# 4_phy2.net
KiCad netlist of a schematic drawn in Altium Designer
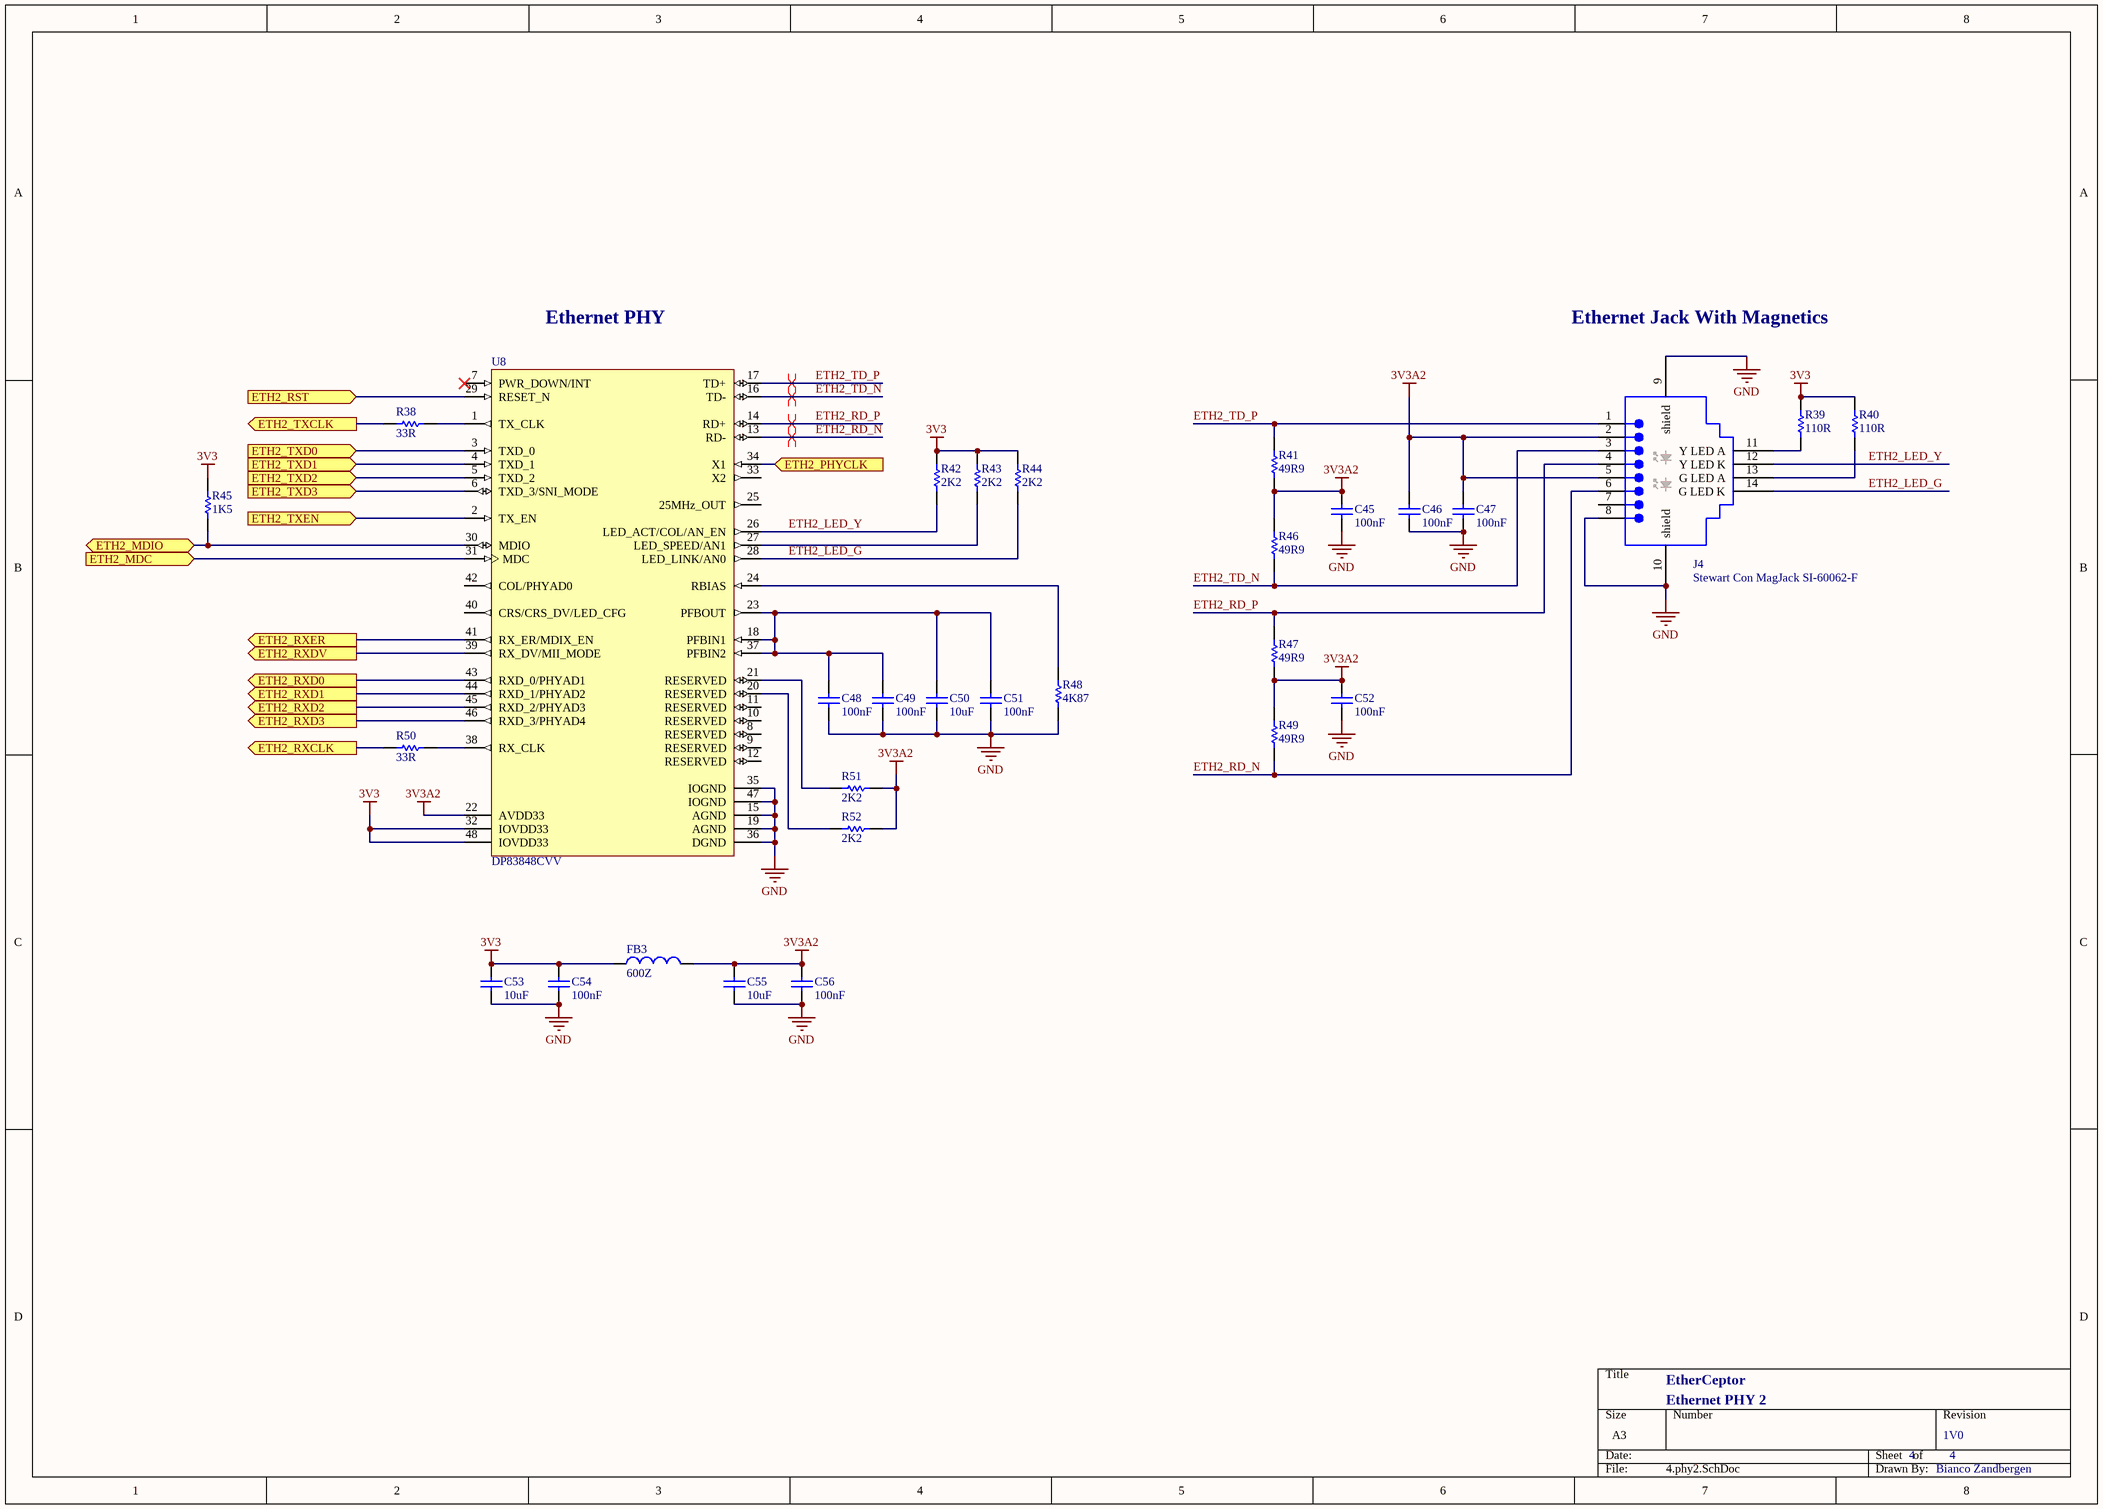
[diagram p0: 4.phy2.SchDoc]

(export (version "E")
  (design (tool "Eeschema 10.0.6"))
  (components
    (comp (ref "C45")
      (value "100nF")
      (footprint "1005[0402]_CAP2")
      (description "Capacitor")
      (fields
        (field (name "MANUFACTURER") "SAMSUNG")
        (field (name "Comment") "Cap")
        (field (name "PUBLISHER") "Altium Limited")
      )
      (libsource (lib "etherceptor") (part "Cap"))
    )
    (comp (ref "C46")
      (value "100nF")
      (footprint "1005[0402]_CAP2")
      (description "Capacitor")
      (fields
        (field (name "MANUFACTURER") "SAMSUNG")
        (field (name "Comment") "Cap")
        (field (name "PUBLISHER") "Altium Limited")
      )
      (libsource (lib "etherceptor") (part "Cap"))
    )
    (comp (ref "C47")
      (value "100nF")
      (footprint "1005[0402]_CAP2")
      (description "Capacitor")
      (fields
        (field (name "MANUFACTURER") "SAMSUNG")
        (field (name "Comment") "Cap")
        (field (name "PUBLISHER") "Altium Limited")
      )
      (libsource (lib "etherceptor") (part "Cap"))
    )
    (comp (ref "C48")
      (value "100nF")
      (footprint "1005[0402]_CAP2")
      (description "Capacitor")
      (fields
        (field (name "MANUFACTURER") "SAMSUNG")
        (field (name "Comment") "Cap")
        (field (name "PUBLISHER") "Altium Limited")
      )
      (libsource (lib "etherceptor") (part "Cap"))
    )
    (comp (ref "C49")
      (value "100nF")
      (footprint "1005[0402]_CAP2")
      (description "Capacitor")
      (fields
        (field (name "MANUFACTURER") "SAMSUNG")
        (field (name "Comment") "Cap")
        (field (name "PUBLISHER") "Altium Limited")
      )
      (libsource (lib "etherceptor") (part "Cap"))
    )
    (comp (ref "C50")
      (value "10uF")
      (footprint "1608[0603]_CAP2")
      (description "Capacitor")
      (fields
        (field (name "MANUFACTURER") "SAMSUNG")
        (field (name "Comment") "Cap")
        (field (name "PUBLISHER") "Altium Limited")
      )
      (libsource (lib "etherceptor") (part "Cap"))
    )
    (comp (ref "C51")
      (value "100nF")
      (footprint "1005[0402]_CAP2")
      (description "Capacitor")
      (fields
        (field (name "MANUFACTURER") "SAMSUNG")
        (field (name "Comment") "Cap")
        (field (name "PUBLISHER") "Altium Limited")
      )
      (libsource (lib "etherceptor") (part "Cap"))
    )
    (comp (ref "C52")
      (value "100nF")
      (footprint "1005[0402]_CAP2")
      (description "Capacitor")
      (fields
        (field (name "MANUFACTURER") "SAMSUNG")
        (field (name "Comment") "Cap")
        (field (name "PUBLISHER") "Altium Limited")
      )
      (libsource (lib "etherceptor") (part "Cap"))
    )
    (comp (ref "C53")
      (value "10uF")
      (footprint "1608[0603]_CAP2")
      (description "Capacitor")
      (fields
        (field (name "MANUFACTURER") "SAMSUNG")
        (field (name "Comment") "Cap")
        (field (name "PUBLISHER") "Altium Limited")
      )
      (libsource (lib "etherceptor") (part "Cap"))
    )
    (comp (ref "C54")
      (value "100nF")
      (footprint "1005[0402]_CAP2")
      (description "Capacitor")
      (fields
        (field (name "MANUFACTURER") "SAMSUNG")
        (field (name "Comment") "Cap")
        (field (name "PUBLISHER") "Altium Limited")
      )
      (libsource (lib "etherceptor") (part "Cap"))
    )
    (comp (ref "C55")
      (value "10uF")
      (footprint "1608[0603]_CAP2")
      (description "Capacitor")
      (fields
        (field (name "MANUFACTURER") "SAMSUNG")
        (field (name "Comment") "Cap")
        (field (name "PUBLISHER") "Altium Limited")
      )
      (libsource (lib "etherceptor") (part "Cap"))
    )
    (comp (ref "C56")
      (value "100nF")
      (footprint "1005[0402]_CAP2")
      (description "Capacitor")
      (fields
        (field (name "MANUFACTURER") "SAMSUNG")
        (field (name "Comment") "Cap")
        (field (name "PUBLISHER") "Altium Limited")
      )
      (libsource (lib "etherceptor") (part "Cap"))
    )
    (comp (ref "FB3")
      (value "600Z")
      (footprint "1005[0402]_FB2")
      (description "Ferrite Bead")
      (fields (field (name "MANUFACTURER") "MURATA") (field (name "PUBLISHER") "Altium Limited"))
      (libsource (lib "etherceptor") (part "Ferrite Bead"))
    )
    (comp (ref "J4")
      (value "Stewart Con MagJack SI-60062-F")
      (footprint "Steward Con RJ45")
      (description "Right Angle,RJ45-Keyed, Flange Mount PCB Jack")
      (fields (field (name "MANUFACTURER") "STEWART CONNECTOR") (field (name "PUBLISHER") "Altium Limited"))
      (libsource (lib "etherceptor") (part "Steward con RJ45 with magnetics"))
    )
    (comp (ref "R38")
      (value "33R")
      (footprint "1005[0402]_RES2")
      (description "Resistor")
      (fields
        (field (name "MANUFACTURER") "PANASONIC")
        (field (name "Comment") "Res")
        (field (name "PUBLISHER") "Altium Limited")
      )
      (libsource (lib "etherceptor") (part "Res"))
    )
    (comp (ref "R39")
      (value "110R")
      (footprint "1005[0402]_RES2")
      (description "Resistor")
      (fields
        (field (name "MANUFACTURER") "PANASONIC")
        (field (name "Comment") "Res")
        (field (name "PUBLISHER") "Altium Limited")
      )
      (libsource (lib "etherceptor") (part "Res"))
    )
    (comp (ref "R40")
      (value "110R")
      (footprint "1005[0402]_RES2")
      (description "Resistor")
      (fields
        (field (name "MANUFACTURER") "PANASONIC")
        (field (name "Comment") "Res")
        (field (name "PUBLISHER") "Altium Limited")
      )
      (libsource (lib "etherceptor") (part "Res"))
    )
    (comp (ref "R41")
      (value "49R9")
      (footprint "1005[0402]_RES2")
      (description "Resistor")
      (fields
        (field (name "MANUFACTURER") "PANASONIC")
        (field (name "Comment") "Res")
        (field (name "PUBLISHER") "Altium Limited")
      )
      (libsource (lib "etherceptor") (part "Res"))
    )
    (comp (ref "R42")
      (value "2K2")
      (footprint "1005[0402]_RES2")
      (description "Resistor")
      (fields
        (field (name "MANUFACTURER") "PANASONIC")
        (field (name "Comment") "Res")
        (field (name "PUBLISHER") "Altium Limited")
      )
      (libsource (lib "etherceptor") (part "Res"))
    )
    (comp (ref "R43")
      (value "2K2")
      (footprint "1005[0402]_RES2")
      (description "Resistor")
      (fields
        (field (name "MANUFACTURER") "PANASONIC")
        (field (name "Comment") "Res")
        (field (name "PUBLISHER") "Altium Limited")
      )
      (libsource (lib "etherceptor") (part "Res"))
    )
    (comp (ref "R44")
      (value "2K2")
      (footprint "1005[0402]_RES2")
      (description "Resistor")
      (fields
        (field (name "MANUFACTURER") "PANASONIC")
        (field (name "Comment") "Res")
        (field (name "PUBLISHER") "Altium Limited")
      )
      (libsource (lib "etherceptor") (part "Res"))
    )
    (comp (ref "R45")
      (value "1K5")
      (footprint "1005[0402]_RES2")
      (description "Resistor")
      (fields
        (field (name "MANUFACTURER") "PANASONIC")
        (field (name "Comment") "Res")
        (field (name "PUBLISHER") "Altium Limited")
      )
      (libsource (lib "etherceptor") (part "Res"))
    )
    (comp (ref "R46")
      (value "49R9")
      (footprint "1005[0402]_RES2")
      (description "Resistor")
      (fields
        (field (name "MANUFACTURER") "PANASONIC")
        (field (name "Comment") "Res")
        (field (name "PUBLISHER") "Altium Limited")
      )
      (libsource (lib "etherceptor") (part "Res"))
    )
    (comp (ref "R47")
      (value "49R9")
      (footprint "1005[0402]_RES2")
      (description "Resistor")
      (fields
        (field (name "MANUFACTURER") "PANASONIC")
        (field (name "Comment") "Res")
        (field (name "PUBLISHER") "Altium Limited")
      )
      (libsource (lib "etherceptor") (part "Res"))
    )
    (comp (ref "R48")
      (value "4K87")
      (footprint "1005[0402]_RES2")
      (description "Resistor")
      (fields
        (field (name "MANUFACTURER") "PANASONIC")
        (field (name "Comment") "Res")
        (field (name "PUBLISHER") "Altium Limited")
      )
      (libsource (lib "etherceptor") (part "Res"))
    )
    (comp (ref "R49")
      (value "49R9")
      (footprint "1005[0402]_RES2")
      (description "Resistor")
      (fields
        (field (name "MANUFACTURER") "PANASONIC")
        (field (name "Comment") "Res")
        (field (name "PUBLISHER") "Altium Limited")
      )
      (libsource (lib "etherceptor") (part "Res"))
    )
    (comp (ref "R50")
      (value "33R")
      (footprint "1005[0402]_RES2")
      (description "Resistor")
      (fields
        (field (name "MANUFACTURER") "PANASONIC")
        (field (name "Comment") "Res")
        (field (name "PUBLISHER") "Altium Limited")
      )
      (libsource (lib "etherceptor") (part "Res"))
    )
    (comp (ref "R51")
      (value "2K2")
      (footprint "1005[0402]_RES2")
      (description "Resistor")
      (fields
        (field (name "MANUFACTURER") "PANASONIC")
        (field (name "Comment") "Res")
        (field (name "PUBLISHER") "Altium Limited")
      )
      (libsource (lib "etherceptor") (part "Res"))
    )
    (comp (ref "R52")
      (value "2K2")
      (footprint "1005[0402]_RES2")
      (description "Resistor")
      (fields
        (field (name "MANUFACTURER") "PANASONIC")
        (field (name "Comment") "Res")
        (field (name "PUBLISHER") "Altium Limited")
      )
      (libsource (lib "etherceptor") (part "Res"))
    )
    (comp (ref "U8")
      (value "DP83848CVV")
      (footprint "TSQFP50P900X900-48M")
      (fields (field (name "MANUFACTURER") "TEXAS INSTRUMENTS") (field (name "PUBLISHER") "Altium Limited"))
      (libsource (lib "etherceptor") (part "DP83848CVV"))
    )
  )
  (nets
    (net (code "1") (name "/ETH2_LED_G") (class "Default")
      (node (ref "J4") (pin "14") (pinfunction "G_LED_K_14") (pintype "passive"))
      (node (ref "R44") (pin "1") (pinfunction "1_1") (pintype "passive"))
      (node (ref "U8") (pin "28") (pinfunction "LED_LINK/AN0_28") (pintype "output"))
    )
    (net (code "2") (name "/ETH2_LED_Y") (class "Default")
      (node (ref "J4") (pin "12") (pinfunction "Y_LED_K_12") (pintype "passive"))
      (node (ref "R42") (pin "1") (pinfunction "1_1") (pintype "passive"))
      (node (ref "U8") (pin "26") (pinfunction "LED_ACT/COL/AN_EN_26") (pintype "output"))
    )
    (net (code "3") (name "/ETH2_MDC") (class "Default")
      (node (ref "U8") (pin "31") (pinfunction "MDC_31") (pintype "input"))
    )
    (net (code "4") (name "/ETH2_MDIO") (class "Default")
      (node (ref "R45") (pin "1") (pinfunction "1_1") (pintype "passive"))
      (node (ref "U8") (pin "30") (pinfunction "MDIO_30") (pintype "bidirectional"))
    )
    (net (code "5") (name "/ETH2_PHYCLK") (class "Default")
      (node (ref "U8") (pin "34") (pinfunction "X1_34") (pintype "input"))
    )
    (net (code "6") (name "/ETH2_RD_N") (class "Default")
      (node (ref "J4") (pin "6") (pinfunction "6_6") (pintype "passive"))
      (node (ref "R49") (pin "1") (pinfunction "1_1") (pintype "passive"))
      (node (ref "U8") (pin "13") (pinfunction "RD-_13") (pintype "bidirectional"))
    )
    (net (code "7") (name "/ETH2_RD_P") (class "Default")
      (node (ref "J4") (pin "4") (pinfunction "4_4") (pintype "passive"))
      (node (ref "R47") (pin "2") (pinfunction "2_2") (pintype "passive"))
      (node (ref "U8") (pin "14") (pinfunction "RD+_14") (pintype "bidirectional"))
    )
    (net (code "8") (name "/ETH2_RST") (class "Default")
      (node (ref "U8") (pin "29") (pinfunction "RESET_N_29") (pintype "input"))
    )
    (net (code "9") (name "/ETH2_RXCLK") (class "Default")
      (node (ref "R50") (pin "1") (pinfunction "1_1") (pintype "passive"))
    )
    (net (code "10") (name "/ETH2_RXD0") (class "Default")
      (node (ref "U8") (pin "43") (pinfunction "RXD_0/PHYAD1_43") (pintype "output"))
    )
    (net (code "11") (name "/ETH2_RXD1") (class "Default")
      (node (ref "U8") (pin "44") (pinfunction "RXD_1/PHYAD2_44") (pintype "output"))
    )
    (net (code "12") (name "/ETH2_RXD2") (class "Default")
      (node (ref "U8") (pin "45") (pinfunction "RXD_2/PHYAD3_45") (pintype "output"))
    )
    (net (code "13") (name "/ETH2_RXD3") (class "Default")
      (node (ref "U8") (pin "46") (pinfunction "RXD_3/PHYAD4_46") (pintype "output"))
    )
    (net (code "14") (name "/ETH2_RXDV") (class "Default")
      (node (ref "U8") (pin "39") (pinfunction "RX_DV/MII_MODE_39") (pintype "output"))
    )
    (net (code "15") (name "/ETH2_RXER") (class "Default")
      (node (ref "U8") (pin "41") (pinfunction "RX_ER/MDIX_EN_41") (pintype "output"))
    )
    (net (code "16") (name "/ETH2_TD_N") (class "Default")
      (node (ref "J4") (pin "3") (pinfunction "3_3") (pintype "passive"))
      (node (ref "R46") (pin "1") (pinfunction "1_1") (pintype "passive"))
      (node (ref "U8") (pin "16") (pinfunction "TD-_16") (pintype "bidirectional"))
    )
    (net (code "17") (name "/ETH2_TD_P") (class "Default")
      (node (ref "J4") (pin "1") (pinfunction "1_1") (pintype "passive"))
      (node (ref "R41") (pin "2") (pinfunction "2_2") (pintype "passive"))
      (node (ref "U8") (pin "17") (pinfunction "TD+_17") (pintype "bidirectional"))
    )
    (net (code "18") (name "/ETH2_TXCLK") (class "Default")
      (node (ref "R38") (pin "1") (pinfunction "1_1") (pintype "passive"))
    )
    (net (code "19") (name "/ETH2_TXD0") (class "Default")
      (node (ref "U8") (pin "3") (pinfunction "TXD_0_3") (pintype "input"))
    )
    (net (code "20") (name "/ETH2_TXD1") (class "Default")
      (node (ref "U8") (pin "4") (pinfunction "TXD_1_4") (pintype "input"))
    )
    (net (code "21") (name "/ETH2_TXD2") (class "Default")
      (node (ref "U8") (pin "5") (pinfunction "TXD_2_5") (pintype "input"))
    )
    (net (code "22") (name "/ETH2_TXD3") (class "Default")
      (node (ref "U8") (pin "6") (pinfunction "TXD_3/SNI_MODE_6") (pintype "bidirectional"))
    )
    (net (code "23") (name "/ETH2_TXEN") (class "Default")
      (node (ref "U8") (pin "2") (pinfunction "TX_EN_2") (pintype "input"))
    )
    (net (code "24") (name "3V3") (class "Default")
      (node (ref "C53") (pin "2") (pinfunction "2_2") (pintype "passive"))
      (node (ref "C54") (pin "2") (pinfunction "2_2") (pintype "passive"))
      (node (ref "FB3") (pin "1") (pinfunction "1_1") (pintype "passive"))
      (node (ref "R39") (pin "2") (pinfunction "2_2") (pintype "passive"))
      (node (ref "R40") (pin "2") (pinfunction "2_2") (pintype "passive"))
      (node (ref "R42") (pin "2") (pinfunction "2_2") (pintype "passive"))
      (node (ref "R43") (pin "2") (pinfunction "2_2") (pintype "passive"))
      (node (ref "R44") (pin "2") (pinfunction "2_2") (pintype "passive"))
      (node (ref "R45") (pin "2") (pinfunction "2_2") (pintype "passive"))
      (node (ref "U8") (pin "32") (pinfunction "IOVDD33_32") (pintype "power_in"))
      (node (ref "U8") (pin "48") (pinfunction "IOVDD33_48") (pintype "power_in"))
    )
    (net (code "25") (name "3V3A2") (class "Default")
      (node (ref "C45") (pin "2") (pinfunction "2_2") (pintype "passive"))
      (node (ref "C46") (pin "2") (pinfunction "2_2") (pintype "passive"))
      (node (ref "C47") (pin "2") (pinfunction "2_2") (pintype "passive"))
      (node (ref "C52") (pin "2") (pinfunction "2_2") (pintype "passive"))
      (node (ref "C55") (pin "2") (pinfunction "2_2") (pintype "passive"))
      (node (ref "C56") (pin "2") (pinfunction "2_2") (pintype "passive"))
      (node (ref "FB3") (pin "2") (pinfunction "2_2") (pintype "passive"))
      (node (ref "J4") (pin "2") (pinfunction "2_2") (pintype "passive"))
      (node (ref "J4") (pin "5") (pinfunction "5_5") (pintype "passive"))
      (node (ref "R41") (pin "1") (pinfunction "1_1") (pintype "passive"))
      (node (ref "R46") (pin "2") (pinfunction "2_2") (pintype "passive"))
      (node (ref "R47") (pin "1") (pinfunction "1_1") (pintype "passive"))
      (node (ref "R49") (pin "2") (pinfunction "2_2") (pintype "passive"))
      (node (ref "R51") (pin "1") (pinfunction "1_1") (pintype "passive"))
      (node (ref "R52") (pin "1") (pinfunction "1_1") (pintype "passive"))
      (node (ref "U8") (pin "22") (pinfunction "AVDD33_22") (pintype "power_in"))
    )
    (net (code "26") (name "GND") (class "Default")
      (node (ref "C45") (pin "1") (pinfunction "1_1") (pintype "passive"))
      (node (ref "C46") (pin "1") (pinfunction "1_1") (pintype "passive"))
      (node (ref "C47") (pin "1") (pinfunction "1_1") (pintype "passive"))
      (node (ref "C48") (pin "1") (pinfunction "1_1") (pintype "passive"))
      (node (ref "C49") (pin "1") (pinfunction "1_1") (pintype "passive"))
      (node (ref "C50") (pin "1") (pinfunction "1_1") (pintype "passive"))
      (node (ref "C51") (pin "1") (pinfunction "1_1") (pintype "passive"))
      (node (ref "C52") (pin "1") (pinfunction "1_1") (pintype "passive"))
      (node (ref "C53") (pin "1") (pinfunction "1_1") (pintype "passive"))
      (node (ref "C54") (pin "1") (pinfunction "1_1") (pintype "passive"))
      (node (ref "C55") (pin "1") (pinfunction "1_1") (pintype "passive"))
      (node (ref "C56") (pin "1") (pinfunction "1_1") (pintype "passive"))
      (node (ref "J4") (pin "10") (pinfunction "shield_10") (pintype "passive"))
      (node (ref "J4") (pin "8") (pinfunction "8_8") (pintype "passive"))
      (node (ref "J4") (pin "9") (pinfunction "shield_9") (pintype "passive"))
      (node (ref "R48") (pin "1") (pinfunction "1_1") (pintype "passive"))
      (node (ref "U8") (pin "15") (pinfunction "AGND_15") (pintype "power_in"))
      (node (ref "U8") (pin "19") (pinfunction "AGND_19") (pintype "power_in"))
      (node (ref "U8") (pin "35") (pinfunction "IOGND_35") (pintype "power_in"))
      (node (ref "U8") (pin "36") (pinfunction "DGND_36") (pintype "power_in"))
      (node (ref "U8") (pin "47") (pinfunction "IOGND_47") (pintype "power_in"))
    )
    (net (code "27") (name "Net-(J4-G_LED_A)") (class "Default")
      (node (ref "J4") (pin "13") (pinfunction "G_LED_A_13") (pintype "passive"))
      (node (ref "R40") (pin "1") (pinfunction "1_1") (pintype "passive"))
    )
    (net (code "28") (name "Net-(J4-Y_LED_A)") (class "Default")
      (node (ref "J4") (pin "11") (pinfunction "Y_LED_A_11") (pintype "passive"))
      (node (ref "R39") (pin "1") (pinfunction "1_1") (pintype "passive"))
    )
    (net (code "29") (name "Net-(R51-Pad2)") (class "Default")
      (node (ref "R51") (pin "2") (pinfunction "2_2") (pintype "passive"))
      (node (ref "U8") (pin "21") (pinfunction "RESERVED_21") (pintype "bidirectional"))
    )
    (net (code "30") (name "Net-(R52-Pad2)") (class "Default")
      (node (ref "R52") (pin "2") (pinfunction "2_2") (pintype "passive"))
      (node (ref "U8") (pin "20") (pinfunction "RESERVED_20") (pintype "bidirectional"))
    )
    (net (code "31") (name "Net-(U8-LED_SPEED{slash}AN1)") (class "Default")
      (node (ref "R43") (pin "1") (pinfunction "1_1") (pintype "passive"))
      (node (ref "U8") (pin "27") (pinfunction "LED_SPEED/AN1_27") (pintype "output"))
    )
    (net (code "32") (name "Net-(U8-PFBIN1)") (class "Default")
      (node (ref "C48") (pin "2") (pinfunction "2_2") (pintype "passive"))
      (node (ref "C49") (pin "2") (pinfunction "2_2") (pintype "passive"))
      (node (ref "C50") (pin "2") (pinfunction "2_2") (pintype "passive"))
      (node (ref "C51") (pin "2") (pinfunction "2_2") (pintype "passive"))
      (node (ref "U8") (pin "18") (pinfunction "PFBIN1_18") (pintype "input"))
      (node (ref "U8") (pin "23") (pinfunction "PFBOUT_23") (pintype "output"))
      (node (ref "U8") (pin "37") (pinfunction "PFBIN2_37") (pintype "input"))
    )
    (net (code "33") (name "Net-(U8-RBIAS)") (class "Default")
      (node (ref "R48") (pin "2") (pinfunction "2_2") (pintype "passive"))
      (node (ref "U8") (pin "24") (pinfunction "RBIAS_24") (pintype "input"))
    )
    (net (code "34") (name "Net-(U8-RX_CLK)") (class "Default")
      (node (ref "R50") (pin "2") (pinfunction "2_2") (pintype "passive"))
      (node (ref "U8") (pin "38") (pinfunction "RX_CLK_38") (pintype "output"))
    )
    (net (code "35") (name "Net-(U8-TX_CLK)") (class "Default")
      (node (ref "R38") (pin "2") (pinfunction "2_2") (pintype "passive"))
      (node (ref "U8") (pin "1") (pinfunction "TX_CLK_1") (pintype "output"))
    )
    (net (code "36") (name "unconnected-(J4-Pad7)") (class "Default")
      (node (ref "J4") (pin "7") (pinfunction "7_7") (pintype "passive"))
    )
    (net (code "37") (name "unconnected-(U8-25MHz_OUT-Pad25)") (class "Default")
      (node (ref "U8") (pin "25") (pinfunction "25MHz_OUT_25") (pintype "output"))
    )
    (net (code "38") (name "unconnected-(U8-COL{slash}PHYAD0-Pad42)") (class "Default")
      (node (ref "U8") (pin "42") (pinfunction "COL/PHYAD0_42") (pintype "output"))
    )
    (net (code "39") (name "unconnected-(U8-CRS{slash}CRS_DV{slash}LED_CFG-Pad40)") (class "Default")
      (node (ref "U8") (pin "40") (pinfunction "CRS/CRS_DV/LED_CFG_40") (pintype "output"))
    )
    (net (code "40") (name "unconnected-(U8-PWR_DOWN{slash}INT-Pad7)") (class "Default")
      (node (ref "U8") (pin "7") (pinfunction "PWR_DOWN/INT_7") (pintype "input+no_connect"))
    )
    (net (code "41") (name "unconnected-(U8-RESERVED-Pad8)") (class "Default")
      (node (ref "U8") (pin "8") (pinfunction "RESERVED_8") (pintype "bidirectional"))
    )
    (net (code "42") (name "unconnected-(U8-RESERVED-Pad9)") (class "Default")
      (node (ref "U8") (pin "9") (pinfunction "RESERVED_9") (pintype "bidirectional"))
    )
    (net (code "43") (name "unconnected-(U8-RESERVED-Pad10)") (class "Default")
      (node (ref "U8") (pin "10") (pinfunction "RESERVED_10") (pintype "bidirectional"))
    )
    (net (code "44") (name "unconnected-(U8-RESERVED-Pad11)") (class "Default")
      (node (ref "U8") (pin "11") (pinfunction "RESERVED_11") (pintype "bidirectional"))
    )
    (net (code "45") (name "unconnected-(U8-RESERVED-Pad12)") (class "Default")
      (node (ref "U8") (pin "12") (pinfunction "RESERVED_12") (pintype "bidirectional"))
    )
    (net (code "46") (name "unconnected-(U8-X2-Pad33)") (class "Default")
      (node (ref "U8") (pin "33") (pinfunction "X2_33") (pintype "output"))
    )
  )
)
